# HS_LS_switch_HI_PWR.net
KiCad netlist of a schematic drawn in Altium Designer
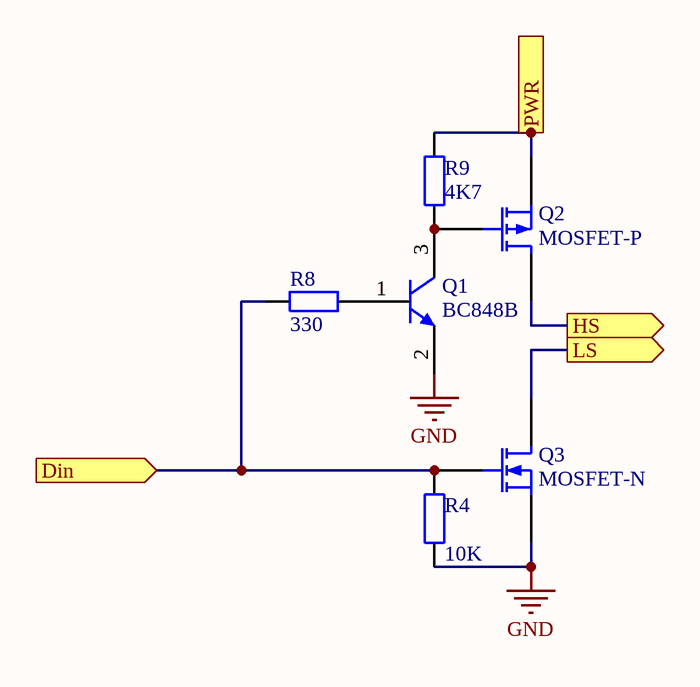
[diagram p0: HS_LS_switch_HI_PWR.SchDoc]

(export (version "E")
  (design (tool "Eeschema 10.0.6"))
  (components
    (comp (ref "Q1")
      (value "BC848B")
      (footprint "SOT23_N")
      (description "NPN Silicon AF Transistor, 30 V VCEO, 100 mA IC, SOT23, Reel, Green")
      (fields (field (name "MANUFACTURER") "Infineon"))
      (libsource (lib "Datalogger") (part "BC848B"))
    )
    (comp (ref "Q2")
      (value "MOSFET-P")
      (footprint "TO-220AB_PMOS_TABDOWN")
      (description "P-Channel MOSFET")
      (libsource (lib "Datalogger") (part "MOSFET-P"))
    )
    (comp (ref "Q3")
      (value "MOSFET-N")
      (footprint "TO-220AB_NMOS_TABDOWN")
      (description "N-Channel MOSFET")
      (libsource (lib "Datalogger") (part "MOSFET-N"))
    )
    (comp (ref "R4")
      (value "10K")
      (footprint "RES-1206_M")
      (description "Resistor")
      (fields (field (name "PUBLISHER") "Altium Limited"))
      (libsource (lib "Datalogger") (part "Res2"))
    )
    (comp (ref "R8")
      (value "330")
      (footprint "RES-1206_M")
      (description "Resistor")
      (fields (field (name "PUBLISHER") "Altium Limited"))
      (libsource (lib "") (part "Res2_1"))
    )
    (comp (ref "R9")
      (value "4K7")
      (footprint "RES-1206_M")
      (description "Resistor")
      (fields (field (name "PUBLISHER") "Altium Limited"))
      (libsource (lib "Datalogger") (part "Res2"))
    )
  )
  (nets
    (net (code "1") (name "/Din") (class "Default")
      (node (ref "Q3") (pin "1") (pinfunction "G_1") (pintype "passive"))
      (node (ref "R4") (pin "2") (pinfunction "2_2") (pintype "passive"))
      (node (ref "R8") (pin "1") (pinfunction "1_1") (pintype "passive"))
    )
    (net (code "2") (name "/HS") (class "Default")
      (node (ref "Q2") (pin "2") (pinfunction "D_2") (pintype "passive"))
    )
    (net (code "3") (name "/LS") (class "Default")
      (node (ref "Q3") (pin "2") (pinfunction "D_2") (pintype "passive"))
    )
    (net (code "4") (name "/PWR") (class "Default")
      (node (ref "Q2") (pin "3") (pinfunction "S_3") (pintype "passive"))
      (node (ref "R9") (pin "2") (pinfunction "2_2") (pintype "passive"))
    )
    (net (code "5") (name "GND") (class "Default")
      (node (ref "Q1") (pin "2") (pinfunction "E_2") (pintype "passive"))
      (node (ref "Q3") (pin "3") (pinfunction "S_3") (pintype "passive"))
      (node (ref "R4") (pin "1") (pinfunction "1_1") (pintype "passive"))
    )
    (net (code "6") (name "Net-(Q1-B)") (class "Default")
      (node (ref "Q1") (pin "1") (pinfunction "B_1") (pintype "passive"))
      (node (ref "R8") (pin "2") (pinfunction "2_2") (pintype "passive"))
    )
    (net (code "7") (name "Net-(Q1-C)") (class "Default")
      (node (ref "Q1") (pin "3") (pinfunction "C_3") (pintype "passive"))
      (node (ref "Q2") (pin "1") (pinfunction "G_1") (pintype "passive"))
      (node (ref "R9") (pin "1") (pinfunction "1_1") (pintype "passive"))
    )
  )
)
